# Si470x-breakout-v13.net
KiCad netlist of a schematic drawn in EAGLE
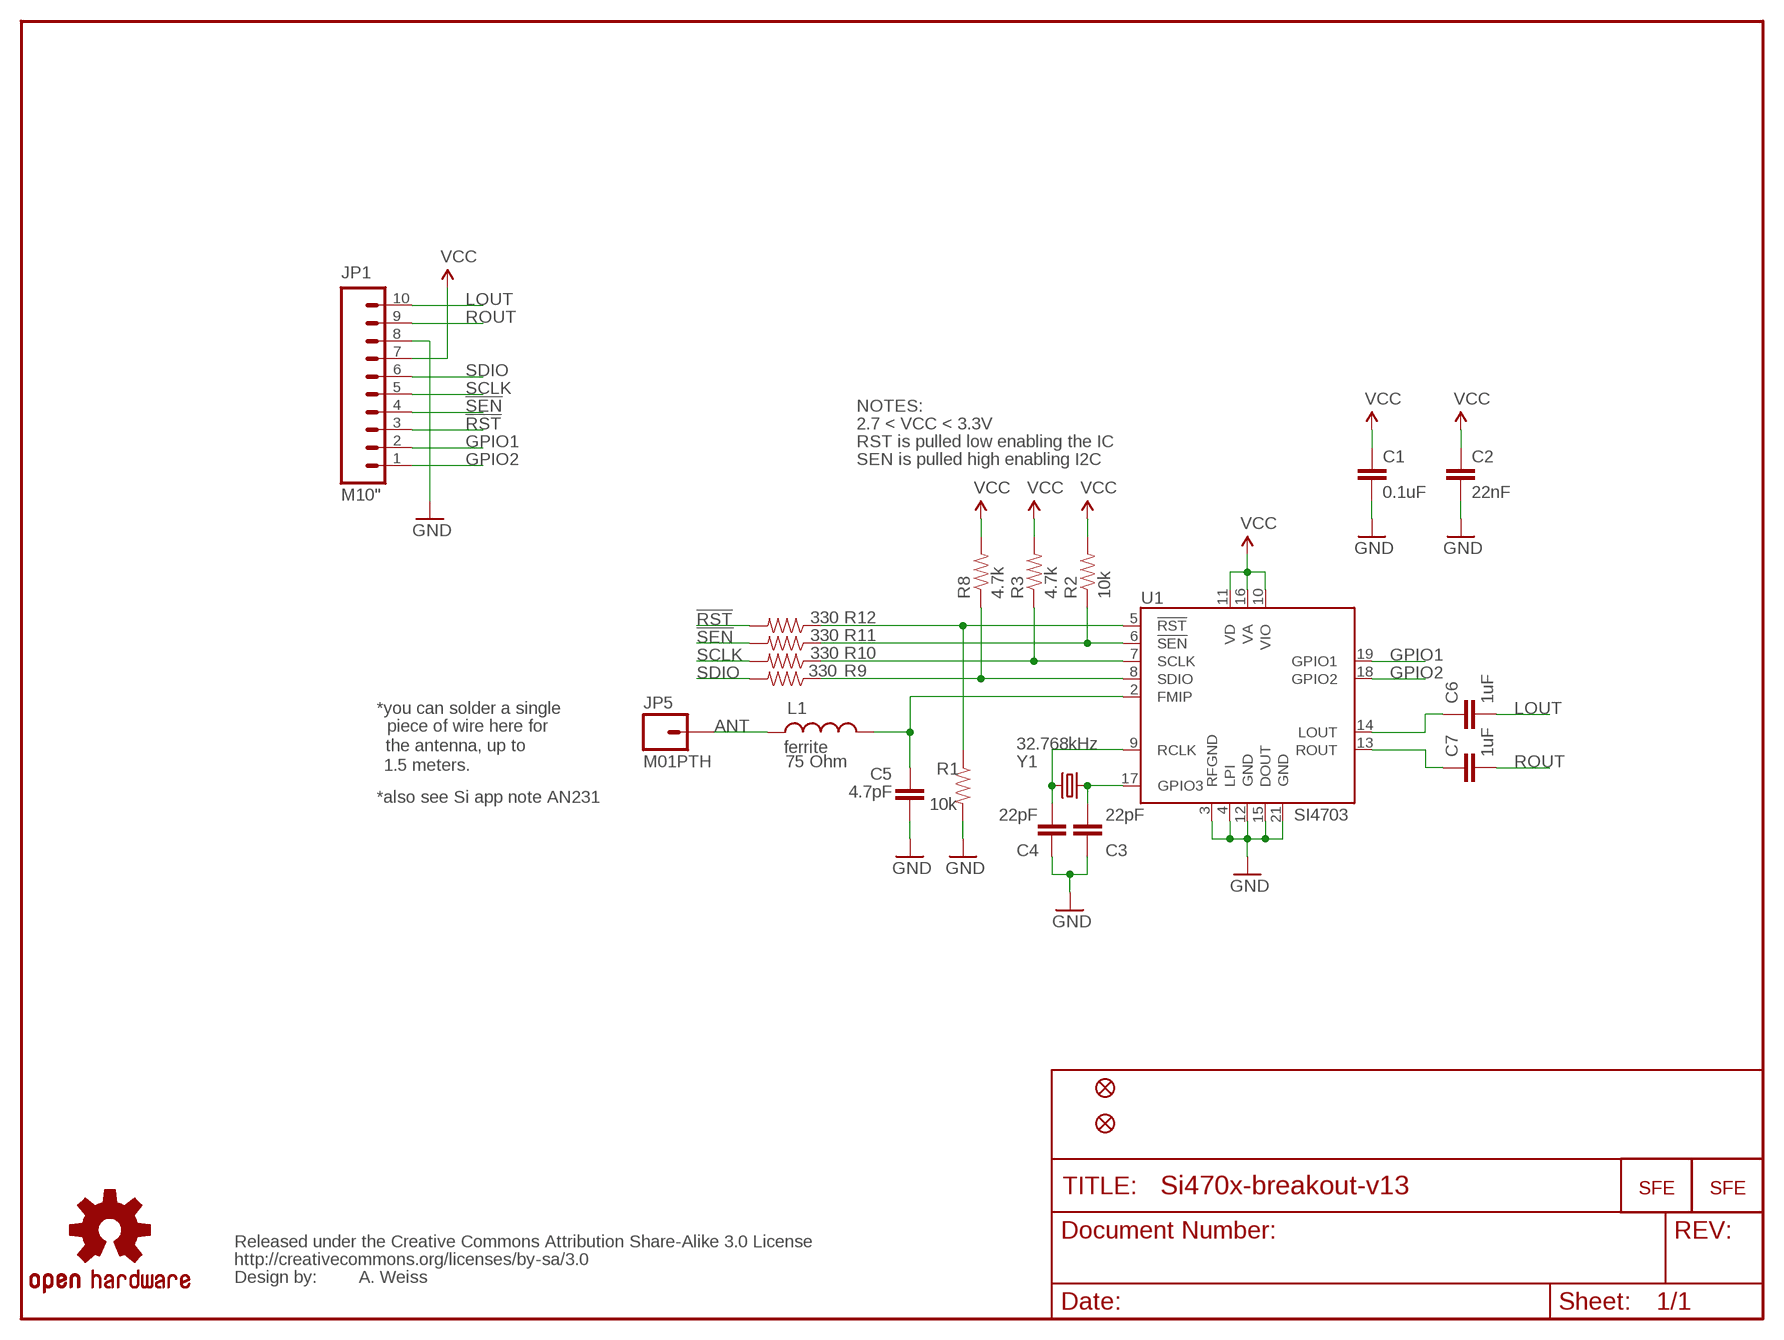
[diagram p0: schematic, sheet 1]

(export (version "E")
  (design (tool "Eeschema 10.0.6"))
  (components
    (comp (ref "C1")
      (value "0.1uF")
      (footprint "eagle-import:0402-CAP")
      (libsource (lib "eagle-import") (part "CAP0402-CAP"))
    )
    (comp (ref "C2")
      (value "22nF")
      (footprint "eagle-import:0402-CAP")
      (libsource (lib "eagle-import") (part "CAP0402-CAP"))
    )
    (comp (ref "C3")
      (value "22pF")
      (footprint "eagle-import:0402-CAP")
      (libsource (lib "eagle-import") (part "CAP0402-CAP"))
    )
    (comp (ref "C4")
      (value "22pF")
      (footprint "eagle-import:0402-CAP")
      (libsource (lib "eagle-import") (part "CAP0402-CAP"))
    )
    (comp (ref "C5")
      (value "4.7pF")
      (footprint "eagle-import:0402-CAP")
      (libsource (lib "eagle-import") (part "CAP0402-CAP"))
    )
    (comp (ref "C6")
      (value "1uF")
      (footprint "eagle-import:0402-CAP")
      (libsource (lib "eagle-import") (part "CAP0402-CAP"))
    )
    (comp (ref "C7")
      (value "1uF")
      (footprint "eagle-import:0402-CAP")
      (libsource (lib "eagle-import") (part "CAP0402-CAP"))
    )
    (comp (ref "JP1")
      (value "M10\"")
      (footprint "eagle-import:1X10")
      (libsource (lib "eagle-import") (part "M10{dblquote}"))
    )
    (comp (ref "JP2")
      (value "LOGO-SFENW2")
      (footprint "eagle-import:SFE-NEW-WEB")
      (libsource (lib "eagle-import") (part "LOGO-SFENW2"))
    )
    (comp (ref "JP3")
      (value "LOGO-SFESK")
      (footprint "eagle-import:SFE-LOGO-FLAME")
      (libsource (lib "eagle-import") (part "LOGO-SFESK"))
    )
    (comp (ref "JP4")
      (value "FIDUCIALUFIDUCIAL")
      (footprint "eagle-import:MICRO-FIDUCIAL")
      (libsource (lib "eagle-import") (part "FIDUCIALUFIDUCIAL"))
    )
    (comp (ref "JP5")
      (value "M01PTH")
      (footprint "eagle-import:1X01")
      (libsource (lib "eagle-import") (part "M01PTH"))
    )
    (comp (ref "JP6")
      (value "FIDUCIALUFIDUCIAL")
      (footprint "eagle-import:MICRO-FIDUCIAL")
      (libsource (lib "eagle-import") (part "FIDUCIALUFIDUCIAL"))
    )
    (comp (ref "L1")
      (value "ferrite")
      (footprint "eagle-import:C0402")
      (fields (field (name "RESISTANCE") "75 Ohm"))
      (libsource (lib "eagle-import") (part "INDUCTOR0402"))
    )
    (comp (ref "R1")
      (value "10k")
      (footprint "eagle-import:0402-RES")
      (libsource (lib "eagle-import") (part "RESISTOR0402-RES"))
    )
    (comp (ref "R2")
      (value "10k")
      (footprint "eagle-import:0402-RES")
      (libsource (lib "eagle-import") (part "RESISTOR0402-RES"))
    )
    (comp (ref "R3")
      (value "4.7k")
      (footprint "eagle-import:0402-RES")
      (libsource (lib "eagle-import") (part "RESISTOR0402-RES"))
    )
    (comp (ref "R8")
      (value "4.7k")
      (footprint "eagle-import:0402-RES")
      (libsource (lib "eagle-import") (part "RESISTOR0402-RES"))
    )
    (comp (ref "R9")
      (value "330")
      (footprint "eagle-import:0402-RES")
      (libsource (lib "eagle-import") (part "RESISTOR0402-RES"))
    )
    (comp (ref "R10")
      (value "330")
      (footprint "eagle-import:0402-RES")
      (libsource (lib "eagle-import") (part "RESISTOR0402-RES"))
    )
    (comp (ref "R11")
      (value "330")
      (footprint "eagle-import:0402-RES")
      (libsource (lib "eagle-import") (part "RESISTOR0402-RES"))
    )
    (comp (ref "R12")
      (value "330")
      (footprint "eagle-import:0402-RES")
      (libsource (lib "eagle-import") (part "RESISTOR0402-RES"))
    )
    (comp (ref "U$1")
      (value "CREATIVE_COMMONS")
      (footprint "eagle-import:CREATIVE_COMMONS")
      (libsource (lib "eagle-import") (part "CREATIVE_COMMONS"))
    )
    (comp (ref "U$3")
      (value "OSHW-LOGOS")
      (footprint "eagle-import:OSHW-LOGO-S")
      (libsource (lib "eagle-import") (part "OSHW-LOGOS"))
    )
    (comp (ref "U1")
      (value "SI4703")
      (footprint "eagle-import:SPARKFUN_SI470X")
      (libsource (lib "eagle-import") (part "SPARKFUN_SI470X"))
    )
    (comp (ref "Y1")
      (value "32.768kHz")
      (footprint "eagle-import:CRYSTAL-32KHZ-SMD")
      (libsource (lib "eagle-import") (part "CRYSTAL32-SMD"))
    )
  )
  (nets
    (net (code "1") (name "/ANT") (class "Default")
      (node (ref "JP5") (pin "1") (pinfunction "1_1") (pintype "passive"))
      (node (ref "L1") (pin "1") (pinfunction "1_1") (pintype "passive"))
    )
    (net (code "2") (name "/GPIO1") (class "Default")
      (node (ref "JP1") (pin "2") (pinfunction "2_2") (pintype "passive"))
      (node (ref "U1") (pin "19") (pinfunction "GPIO1_19") (pintype "bidirectional"))
    )
    (net (code "3") (name "/GPIO2") (class "Default")
      (node (ref "JP1") (pin "1") (pinfunction "1_1") (pintype "passive"))
      (node (ref "U1") (pin "18") (pinfunction "GPIO2_18") (pintype "bidirectional"))
    )
    (net (code "4") (name "/LOUT") (class "Default")
      (node (ref "C6") (pin "2") (pinfunction "2_2") (pintype "passive"))
      (node (ref "JP1") (pin "10") (pinfunction "10_10") (pintype "passive"))
    )
    (net (code "5") (name "/ROUT") (class "Default")
      (node (ref "C7") (pin "2") (pinfunction "2_2") (pintype "passive"))
      (node (ref "JP1") (pin "9") (pinfunction "9_9") (pintype "passive"))
    )
    (net (code "6") (name "/SCLK") (class "Default")
      (node (ref "JP1") (pin "5") (pinfunction "5_5") (pintype "passive"))
      (node (ref "R10") (pin "2") (pinfunction "2_2") (pintype "passive"))
    )
    (net (code "7") (name "/SDIO") (class "Default")
      (node (ref "JP1") (pin "6") (pinfunction "6_6") (pintype "passive"))
      (node (ref "R9") (pin "2") (pinfunction "2_2") (pintype "passive"))
    )
    (net (code "8") (name "/~{RST}") (class "Default")
      (node (ref "JP1") (pin "3") (pinfunction "3_3") (pintype "passive"))
      (node (ref "R12") (pin "2") (pinfunction "2_2") (pintype "passive"))
    )
    (net (code "9") (name "/~{SEN}") (class "Default")
      (node (ref "JP1") (pin "4") (pinfunction "4_4") (pintype "passive"))
      (node (ref "R11") (pin "2") (pinfunction "2_2") (pintype "passive"))
    )
    (net (code "10") (name "GND") (class "Default")
      (node (ref "C1") (pin "2") (pinfunction "2_2") (pintype "passive"))
      (node (ref "C2") (pin "2") (pinfunction "2_2") (pintype "passive"))
      (node (ref "C3") (pin "1") (pinfunction "1_1") (pintype "passive"))
      (node (ref "C4") (pin "1") (pinfunction "1_1") (pintype "passive"))
      (node (ref "C5") (pin "2") (pinfunction "2_2") (pintype "passive"))
      (node (ref "JP1") (pin "8") (pinfunction "8_8") (pintype "passive"))
      (node (ref "R1") (pin "2") (pinfunction "2_2") (pintype "passive"))
      (node (ref "U1") (pin "12") (pinfunction "GND_12") (pintype "bidirectional"))
      (node (ref "U1") (pin "15") (pinfunction "DOUT_15") (pintype "bidirectional"))
      (node (ref "U1") (pin "21") (pinfunction "GND_21") (pintype "bidirectional"))
      (node (ref "U1") (pin "3") (pinfunction "RFGND_3") (pintype "bidirectional"))
      (node (ref "U1") (pin "4") (pinfunction "LPI_4") (pintype "bidirectional"))
    )
    (net (code "11") (name "Net-(U1-FMIP)") (class "Default")
      (node (ref "C5") (pin "1") (pinfunction "1_1") (pintype "passive"))
      (node (ref "L1") (pin "2") (pinfunction "2_2") (pintype "passive"))
      (node (ref "U1") (pin "2") (pinfunction "FMIP_2") (pintype "bidirectional"))
    )
    (net (code "12") (name "Net-(U1-GPIO3)") (class "Default")
      (node (ref "C3") (pin "2") (pinfunction "2_2") (pintype "passive"))
      (node (ref "U1") (pin "17") (pinfunction "GPIO3_17") (pintype "bidirectional"))
      (node (ref "Y1") (pin "X1") (pinfunction "1_X1") (pintype "passive"))
    )
    (net (code "13") (name "Net-(U1-LOUT)") (class "Default")
      (node (ref "C6") (pin "1") (pinfunction "1_1") (pintype "passive"))
      (node (ref "U1") (pin "14") (pinfunction "LOUT_14") (pintype "bidirectional"))
    )
    (net (code "14") (name "Net-(U1-RCLK)") (class "Default")
      (node (ref "C4") (pin "2") (pinfunction "2_2") (pintype "passive"))
      (node (ref "U1") (pin "9") (pinfunction "RCLK_9") (pintype "bidirectional"))
      (node (ref "Y1") (pin "X2") (pinfunction "2_X2") (pintype "passive"))
    )
    (net (code "15") (name "Net-(U1-ROUT)") (class "Default")
      (node (ref "C7") (pin "1") (pinfunction "1_1") (pintype "passive"))
      (node (ref "U1") (pin "13") (pinfunction "ROUT_13") (pintype "bidirectional"))
    )
    (net (code "16") (name "Net-(U1-SCLK)") (class "Default")
      (node (ref "R10") (pin "1") (pinfunction "1_1") (pintype "passive"))
      (node (ref "R3") (pin "1") (pinfunction "1_1") (pintype "passive"))
      (node (ref "U1") (pin "7") (pinfunction "SCLK_7") (pintype "bidirectional"))
    )
    (net (code "17") (name "Net-(U1-SDIO)") (class "Default")
      (node (ref "R8") (pin "1") (pinfunction "1_1") (pintype "passive"))
      (node (ref "R9") (pin "1") (pinfunction "1_1") (pintype "passive"))
      (node (ref "U1") (pin "8") (pinfunction "SDIO_8") (pintype "bidirectional"))
    )
    (net (code "18") (name "Net-(U1-~{RST})") (class "Default")
      (node (ref "R1") (pin "1") (pinfunction "1_1") (pintype "passive"))
      (node (ref "R12") (pin "1") (pinfunction "1_1") (pintype "passive"))
      (node (ref "U1") (pin "5") (pinfunction "~{RST}_5") (pintype "bidirectional"))
    )
    (net (code "19") (name "Net-(U1-~{SEN})") (class "Default")
      (node (ref "R11") (pin "1") (pinfunction "1_1") (pintype "passive"))
      (node (ref "R2") (pin "1") (pinfunction "1_1") (pintype "passive"))
      (node (ref "U1") (pin "6") (pinfunction "~{SEN}_6") (pintype "bidirectional"))
    )
    (net (code "20") (name "VCC") (class "Default")
      (node (ref "C1") (pin "1") (pinfunction "1_1") (pintype "passive"))
      (node (ref "C2") (pin "1") (pinfunction "1_1") (pintype "passive"))
      (node (ref "JP1") (pin "7") (pinfunction "7_7") (pintype "passive"))
      (node (ref "R2") (pin "2") (pinfunction "2_2") (pintype "passive"))
      (node (ref "R3") (pin "2") (pinfunction "2_2") (pintype "passive"))
      (node (ref "R8") (pin "2") (pinfunction "2_2") (pintype "passive"))
      (node (ref "U1") (pin "10") (pinfunction "VIO_10") (pintype "bidirectional"))
      (node (ref "U1") (pin "11") (pinfunction "VD_11") (pintype "bidirectional"))
      (node (ref "U1") (pin "16") (pinfunction "VA_16") (pintype "bidirectional"))
    )
  )
)
